# regulators.net
KiCad netlist of a schematic drawn in Altium Designer
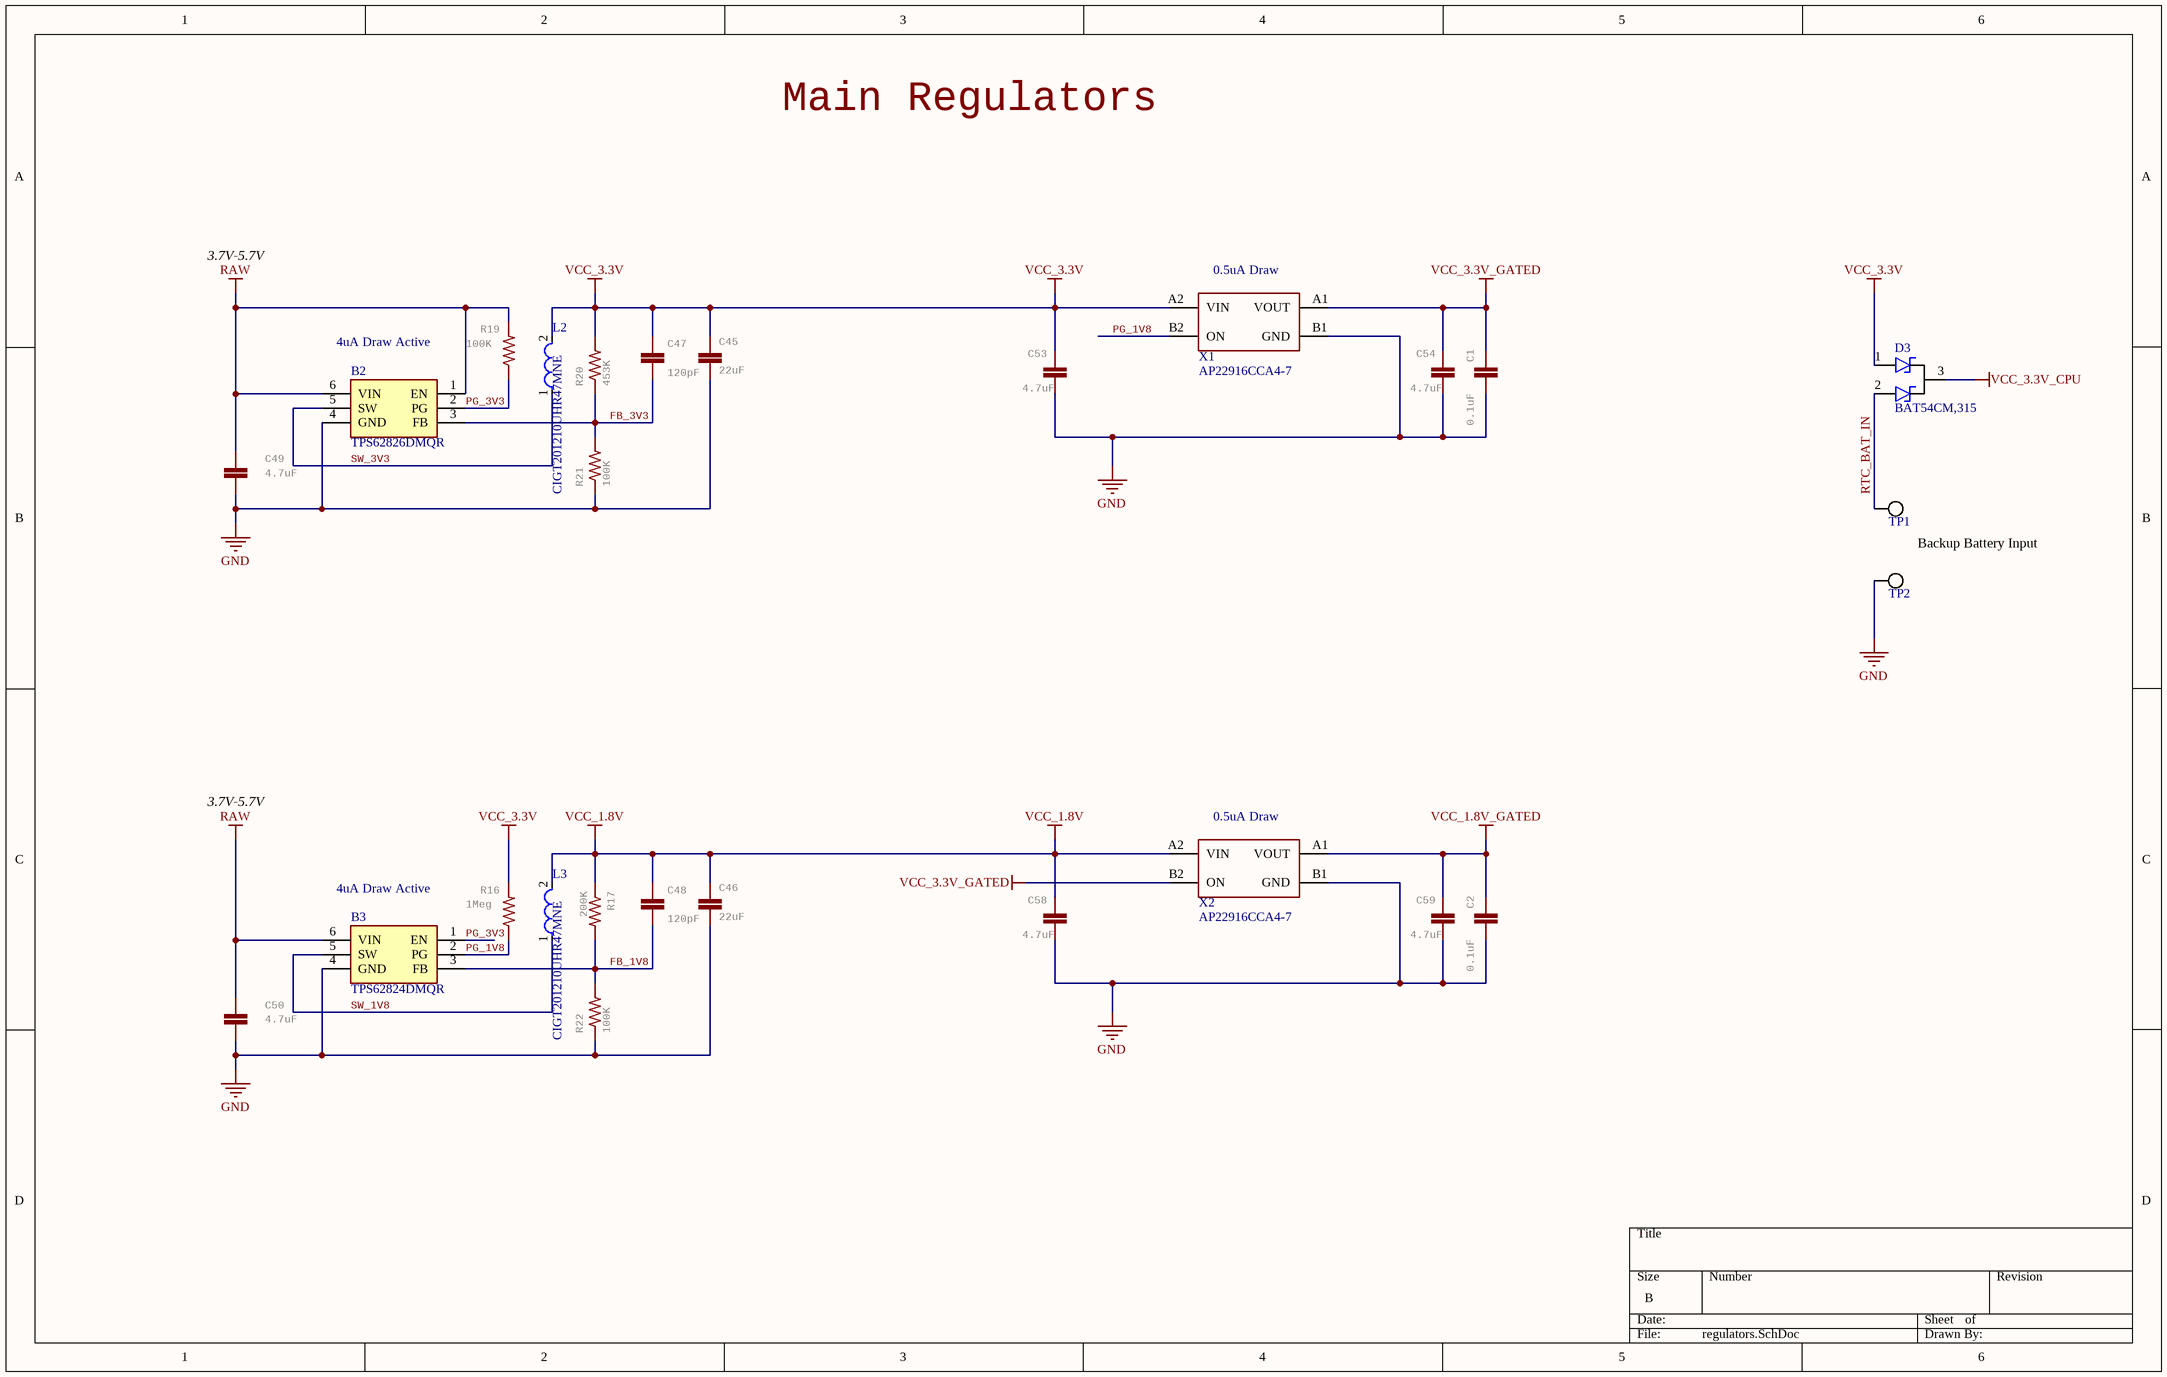
[diagram p0: regulators.SchDoc]

(export (version "E")
  (design (tool "Eeschema 10.0.6"))
  (components
    (comp (ref "B2")
      (value "TPS62826DMQR")
      (footprint "TPS62826ADMQR")
      (fields (field (name "MOUSER PART NUMBER") "595-TPS62826DMQR"))
      (libsource (lib "openmv-ae3") (part "TPS62826ADMQR"))
    )
    (comp (ref "B3")
      (value "TPS62824DMQR")
      (footprint "TPS62826ADMQR")
      (fields (field (name "MOUSER PART NUMBER") "595-TPS62824DMQR"))
      (libsource (lib "openmv-ae3") (part "TPS62826ADMQR"))
    )
    (comp (ref "C1")
      (value "0.1uF")
      (footprint "0402-CAP")
      (description "CAPACITOR, European symbol")
      (fields (field (name "MPN") "C0402C104Z4VAC"))
      (libsource (lib "openmv-ae3") (part "C-EUC0201"))
    )
    (comp (ref "C2")
      (value "0.1uF")
      (footprint "0402-CAP")
      (description "CAPACITOR, European symbol")
      (fields (field (name "MPN") "C0402C104Z4VAC"))
      (libsource (lib "openmv-ae3") (part "C-EUC0201"))
    )
    (comp (ref "C45")
      (value "22uF")
      (footprint "0805")
      (fields (field (name "MPN") "CL21A226MQQNNNE"))
      (libsource (lib "openmv-ae3") (part "22UF-0805-6.3V-20%"))
    )
    (comp (ref "C46")
      (value "22uF")
      (footprint "0805")
      (fields (field (name "MPN") "CL21A226MQQNNNE"))
      (libsource (lib "openmv-ae3") (part "22UF-0805-6.3V-20%"))
    )
    (comp (ref "C47")
      (value "120pF")
      (footprint "C0201")
      (fields (field (name "LIBRARYNAME") "sfe"))
      (libsource (lib "openmv-ae3") (part "CAP0402-CAP"))
    )
    (comp (ref "C48")
      (value "120pF")
      (footprint "C0201")
      (fields (field (name "LIBRARYNAME") "sfe"))
      (libsource (lib "openmv-ae3") (part "CAP0402-CAP"))
    )
    (comp (ref "C49")
      (value "4.7uF")
      (footprint "0402-CAP")
      (description "CapacitorStandard 0603 ceramic capacitor, and 0.1\" leaded capacitor.")
      (fields (field (name "MPN") "JMK105BBJ475MV-F") (field (name "LIBRARYNAME") "sfe"))
      (libsource (lib "openmv-ae3") (part "CAP0402-CAP"))
    )
    (comp (ref "C50")
      (value "4.7uF")
      (footprint "0402-CAP")
      (description "CapacitorStandard 0603 ceramic capacitor, and 0.1\" leaded capacitor.")
      (fields (field (name "MPN") "JMK105BBJ475MV-F") (field (name "LIBRARYNAME") "sfe"))
      (libsource (lib "openmv-ae3") (part "CAP0402-CAP"))
    )
    (comp (ref "C53")
      (value "4.7uF")
      (footprint "0402-CAP")
      (description "CapacitorStandard 0603 ceramic capacitor, and 0.1\" leaded capacitor.")
      (fields (field (name "MPN") "JMK105BBJ475MV-F") (field (name "LIBRARYNAME") "sfe"))
      (libsource (lib "") (part "CAP0402-CAP_1"))
    )
    (comp (ref "C54")
      (value "4.7uF")
      (footprint "0402-CAP")
      (description "CapacitorStandard 0603 ceramic capacitor, and 0.1\" leaded capacitor.")
      (fields (field (name "MPN") "JMK105BBJ475MV-F") (field (name "LIBRARYNAME") "sfe"))
      (libsource (lib "") (part "CAP0402-CAP_1"))
    )
    (comp (ref "C58")
      (value "4.7uF")
      (footprint "0402-CAP")
      (description "CapacitorStandard 0603 ceramic capacitor, and 0.1\" leaded capacitor.")
      (fields (field (name "MPN") "JMK105BBJ475MV-F") (field (name "LIBRARYNAME") "sfe"))
      (libsource (lib "") (part "CAP0402-CAP_1"))
    )
    (comp (ref "C59")
      (value "4.7uF")
      (footprint "0402-CAP")
      (description "CapacitorStandard 0603 ceramic capacitor, and 0.1\" leaded capacitor.")
      (fields (field (name "MPN") "JMK105BBJ475MV-F") (field (name "LIBRARYNAME") "sfe"))
      (libsource (lib "") (part "CAP0402-CAP_1"))
    )
    (comp (ref "D3")
      (value "Dual Schottky")
      (footprint "DFN1006")
      (fields (field (name "MPN") "BAT54CM,315") (field (name "PART NUMBER") "BAT54CLT3G"))
      (libsource (lib "openmv-ae3") (part "Dual Schottky"))
    )
    (comp (ref "L2")
      (value "CIGT201210UHR47MNE")
      (footprint "0805")
      (description "Power Inductor : LxW size(mm) 2012 Thickness1 Inductance (uH) 20%: 0.47")
      (fields (field (name "TOLERANCE") "20%"))
      (libsource (lib "openmv-ae3") (part "CMP-00002-1"))
    )
    (comp (ref "L3")
      (value "CIGT201210UHR47MNE")
      (footprint "0805")
      (description "Power Inductor : LxW size(mm) 2012 Thickness1 Inductance (uH) 20%: 0.47")
      (fields (field (name "TOLERANCE") "20%"))
      (libsource (lib "openmv-ae3") (part "CMP-00002-1"))
    )
    (comp (ref "R16")
      (value "1Meg")
      (footprint "R0201")
      (fields (field (name "LIBRARYNAME") "sfe"))
      (libsource (lib "openmv-ae3") (part "RESISTOR0402-RES"))
    )
    (comp (ref "R17")
      (value "200K")
      (footprint "R0201")
      (fields (field (name "LIBRARYNAME") "sfe"))
      (libsource (lib "openmv-ae3") (part "RESISTOR0402-RES"))
    )
    (comp (ref "R19")
      (value "100K")
      (footprint "R0201")
      (fields (field (name "LIBRARYNAME") "sfe"))
      (libsource (lib "openmv-ae3") (part "RESISTOR0402-RES"))
    )
    (comp (ref "R20")
      (value "453K")
      (footprint "R0201")
      (fields (field (name "LIBRARYNAME") "sfe"))
      (libsource (lib "openmv-ae3") (part "RESISTOR0402-RES"))
    )
    (comp (ref "R21")
      (value "100K")
      (footprint "R0201")
      (fields (field (name "LIBRARYNAME") "sfe"))
      (libsource (lib "openmv-ae3") (part "RESISTOR0402-RES"))
    )
    (comp (ref "R22")
      (value "100K")
      (footprint "R0201")
      (fields (field (name "LIBRARYNAME") "sfe"))
      (libsource (lib "openmv-ae3") (part "RESISTOR0402-RES"))
    )
    (comp (ref "TP1") (value "TP") (footprint "TP_1p8") (libsource (lib "openmv-ae3") (part "TP")))
    (comp (ref "TP2") (value "TP") (footprint "TP_1p8") (libsource (lib "openmv-ae3") (part "TP")))
    (comp (ref "X1")
      (value "PMOS Load Switch")
      (footprint "AP22916CCA4-7")
      (fields (field (name "MPN") "AP22916CCA4-7") (field (name "MF") "Diodes Inc"))
      (libsource (lib "openmv-ae3") (part "AP22916CCA4-7"))
    )
    (comp (ref "X2")
      (value "PMOS Load Switch")
      (footprint "AP22916CCA4-7")
      (fields (field (name "MPN") "AP22916CCA4-7") (field (name "MF") "Diodes Inc"))
      (libsource (lib "openmv-ae3") (part "AP22916CCA4-7"))
    )
  )
  (nets
    (net (code "1") (name "/FB_1V8") (class "Default")
      (node (ref "B3") (pin "3") (pinfunction "FB_3") (pintype "passive"))
      (node (ref "C48") (pin "1") (pinfunction "1_1") (pintype "passive"))
      (node (ref "R17") (pin "2") (pinfunction "2_2") (pintype "passive"))
      (node (ref "R22") (pin "2") (pinfunction "2_2") (pintype "passive"))
    )
    (net (code "2") (name "/FB_3V3") (class "Default")
      (node (ref "B2") (pin "3") (pinfunction "FB_3") (pintype "passive"))
      (node (ref "C47") (pin "1") (pinfunction "1_1") (pintype "passive"))
      (node (ref "R20") (pin "1") (pinfunction "1_1") (pintype "passive"))
      (node (ref "R21") (pin "2") (pinfunction "2_2") (pintype "passive"))
    )
    (net (code "3") (name "/PG_1V8") (class "Default")
      (node (ref "B3") (pin "2") (pinfunction "PG_2") (pintype "passive"))
      (node (ref "R16") (pin "1") (pinfunction "1_1") (pintype "passive"))
      (node (ref "X1") (pin "B2") (pinfunction "ON_B2") (pintype "passive"))
    )
    (net (code "4") (name "/PG_3V3") (class "Default")
      (node (ref "B2") (pin "2") (pinfunction "PG_2") (pintype "passive"))
      (node (ref "B3") (pin "1") (pinfunction "EN_1") (pintype "passive"))
      (node (ref "R19") (pin "1") (pinfunction "1_1") (pintype "passive"))
    )
    (net (code "5") (name "/RTC_BAT_IN") (class "Default")
      (node (ref "D3") (pin "2") (pinfunction "2_2") (pintype "passive"))
      (node (ref "TP1") (pin "1") (pinfunction "1_1") (pintype "passive"))
    )
    (net (code "6") (name "/SW_1V8") (class "Default")
      (node (ref "B3") (pin "5") (pinfunction "SW_5") (pintype "passive"))
      (node (ref "L3") (pin "1") (pinfunction "1_1") (pintype "passive"))
    )
    (net (code "7") (name "/SW_3V3") (class "Default")
      (node (ref "B2") (pin "5") (pinfunction "SW_5") (pintype "passive"))
      (node (ref "L2") (pin "1") (pinfunction "1_1") (pintype "passive"))
    )
    (net (code "8") (name "GND") (class "Default")
      (node (ref "B2") (pin "4") (pinfunction "GND_4") (pintype "passive"))
      (node (ref "B3") (pin "4") (pinfunction "GND_4") (pintype "passive"))
      (node (ref "C1") (pin "2") (pinfunction "2_2") (pintype "passive"))
      (node (ref "C2") (pin "2") (pinfunction "2_2") (pintype "passive"))
      (node (ref "C45") (pin "2") (pinfunction "2_2") (pintype "passive"))
      (node (ref "C46") (pin "2") (pinfunction "2_2") (pintype "passive"))
      (node (ref "C49") (pin "1") (pinfunction "1_1") (pintype "passive"))
      (node (ref "C50") (pin "1") (pinfunction "1_1") (pintype "passive"))
      (node (ref "C53") (pin "2") (pinfunction "2_2") (pintype "passive"))
      (node (ref "C54") (pin "2") (pinfunction "2_2") (pintype "passive"))
      (node (ref "C58") (pin "2") (pinfunction "2_2") (pintype "passive"))
      (node (ref "C59") (pin "2") (pinfunction "2_2") (pintype "passive"))
      (node (ref "R21") (pin "1") (pinfunction "1_1") (pintype "passive"))
      (node (ref "R22") (pin "1") (pinfunction "1_1") (pintype "passive"))
      (node (ref "TP2") (pin "1") (pinfunction "1_1") (pintype "passive"))
      (node (ref "X1") (pin "B1") (pinfunction "GND_B1") (pintype "passive"))
      (node (ref "X2") (pin "B1") (pinfunction "GND_B1") (pintype "passive"))
    )
    (net (code "9") (name "RAW") (class "Default")
      (node (ref "B2") (pin "1") (pinfunction "EN_1") (pintype "passive"))
      (node (ref "B2") (pin "6") (pinfunction "VIN_6") (pintype "passive"))
      (node (ref "B3") (pin "6") (pinfunction "VIN_6") (pintype "passive"))
      (node (ref "C49") (pin "2") (pinfunction "2_2") (pintype "passive"))
      (node (ref "C50") (pin "2") (pinfunction "2_2") (pintype "passive"))
      (node (ref "R19") (pin "2") (pinfunction "2_2") (pintype "passive"))
    )
    (net (code "10") (name "VCC_1.8V") (class "Default")
      (node (ref "C46") (pin "1") (pinfunction "1_1") (pintype "passive"))
      (node (ref "C48") (pin "2") (pinfunction "2_2") (pintype "passive"))
      (node (ref "C58") (pin "1") (pinfunction "1_1") (pintype "passive"))
      (node (ref "L3") (pin "2") (pinfunction "2_2") (pintype "passive"))
      (node (ref "R17") (pin "1") (pinfunction "1_1") (pintype "passive"))
      (node (ref "X2") (pin "A2") (pinfunction "VIN_A2") (pintype "passive"))
    )
    (net (code "11") (name "VCC_1.8V_GATED") (class "Default")
      (node (ref "C2") (pin "1") (pinfunction "1_1") (pintype "passive"))
      (node (ref "C59") (pin "1") (pinfunction "1_1") (pintype "passive"))
      (node (ref "X2") (pin "A1") (pinfunction "VOUT_A1") (pintype "passive"))
    )
    (net (code "12") (name "VCC_3.3V") (class "Default")
      (node (ref "C45") (pin "1") (pinfunction "1_1") (pintype "passive"))
      (node (ref "C47") (pin "2") (pinfunction "2_2") (pintype "passive"))
      (node (ref "C53") (pin "1") (pinfunction "1_1") (pintype "passive"))
      (node (ref "D3") (pin "1") (pinfunction "1_1") (pintype "passive"))
      (node (ref "L2") (pin "2") (pinfunction "2_2") (pintype "passive"))
      (node (ref "R16") (pin "2") (pinfunction "2_2") (pintype "passive"))
      (node (ref "R20") (pin "2") (pinfunction "2_2") (pintype "passive"))
      (node (ref "X1") (pin "A2") (pinfunction "VIN_A2") (pintype "passive"))
    )
    (net (code "13") (name "VCC_3.3V_CPU") (class "Default")
      (node (ref "D3") (pin "3") (pinfunction "3_3") (pintype "passive"))
    )
    (net (code "14") (name "VCC_3.3V_GATED") (class "Default")
      (node (ref "C1") (pin "1") (pinfunction "1_1") (pintype "passive"))
      (node (ref "C54") (pin "1") (pinfunction "1_1") (pintype "passive"))
      (node (ref "X1") (pin "A1") (pinfunction "VOUT_A1") (pintype "passive"))
      (node (ref "X2") (pin "B2") (pinfunction "ON_B2") (pintype "passive"))
    )
  )
)
